# lia_2-0.net
KiCad netlist of a schematic drawn in EAGLE
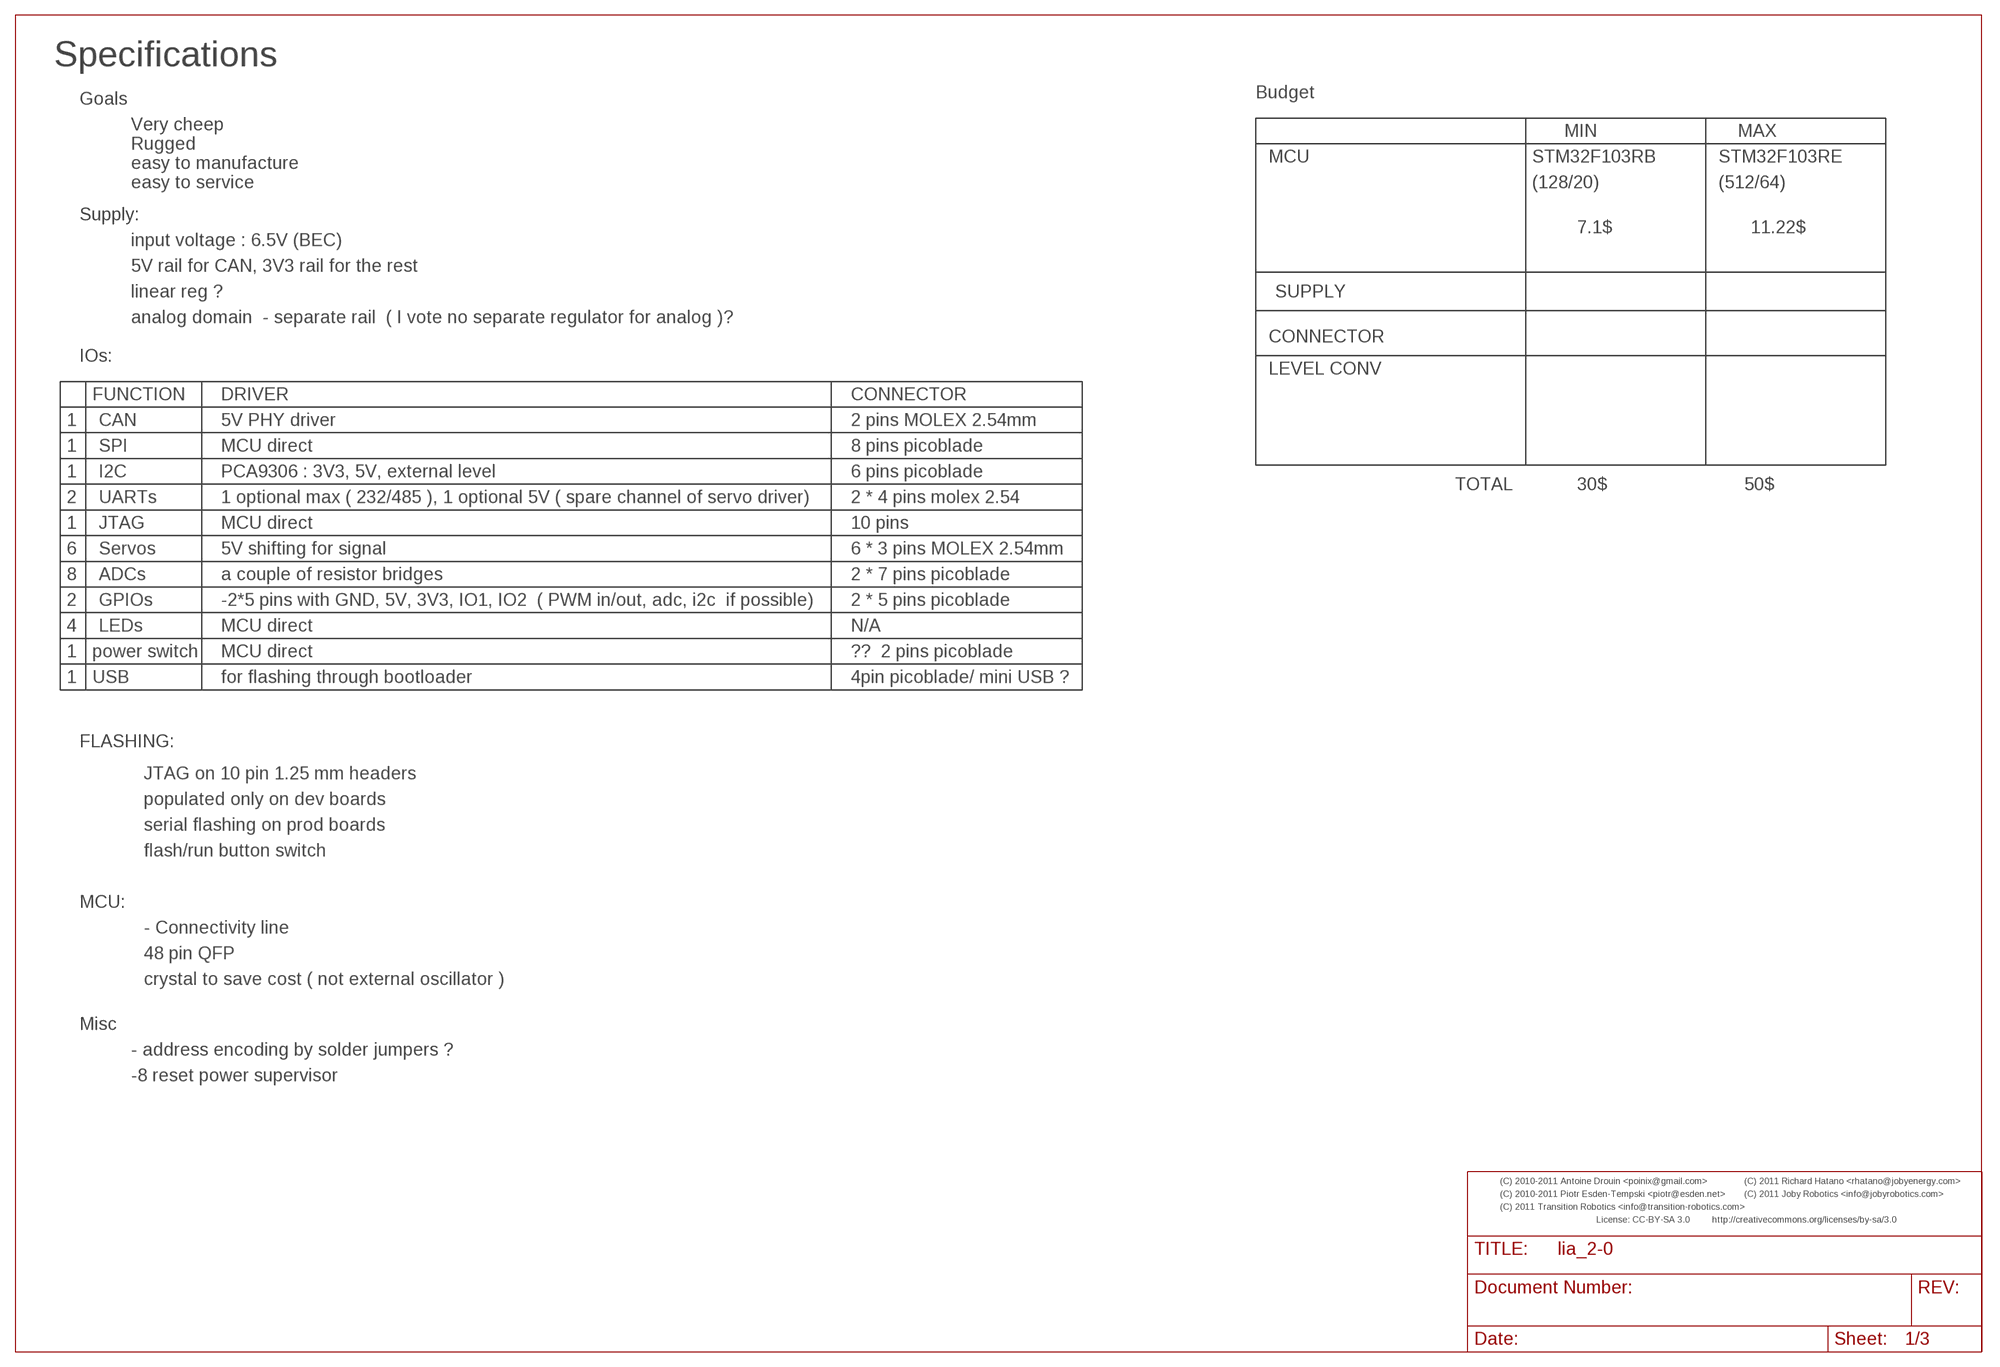
[diagram p0: schematic, sheet 1]
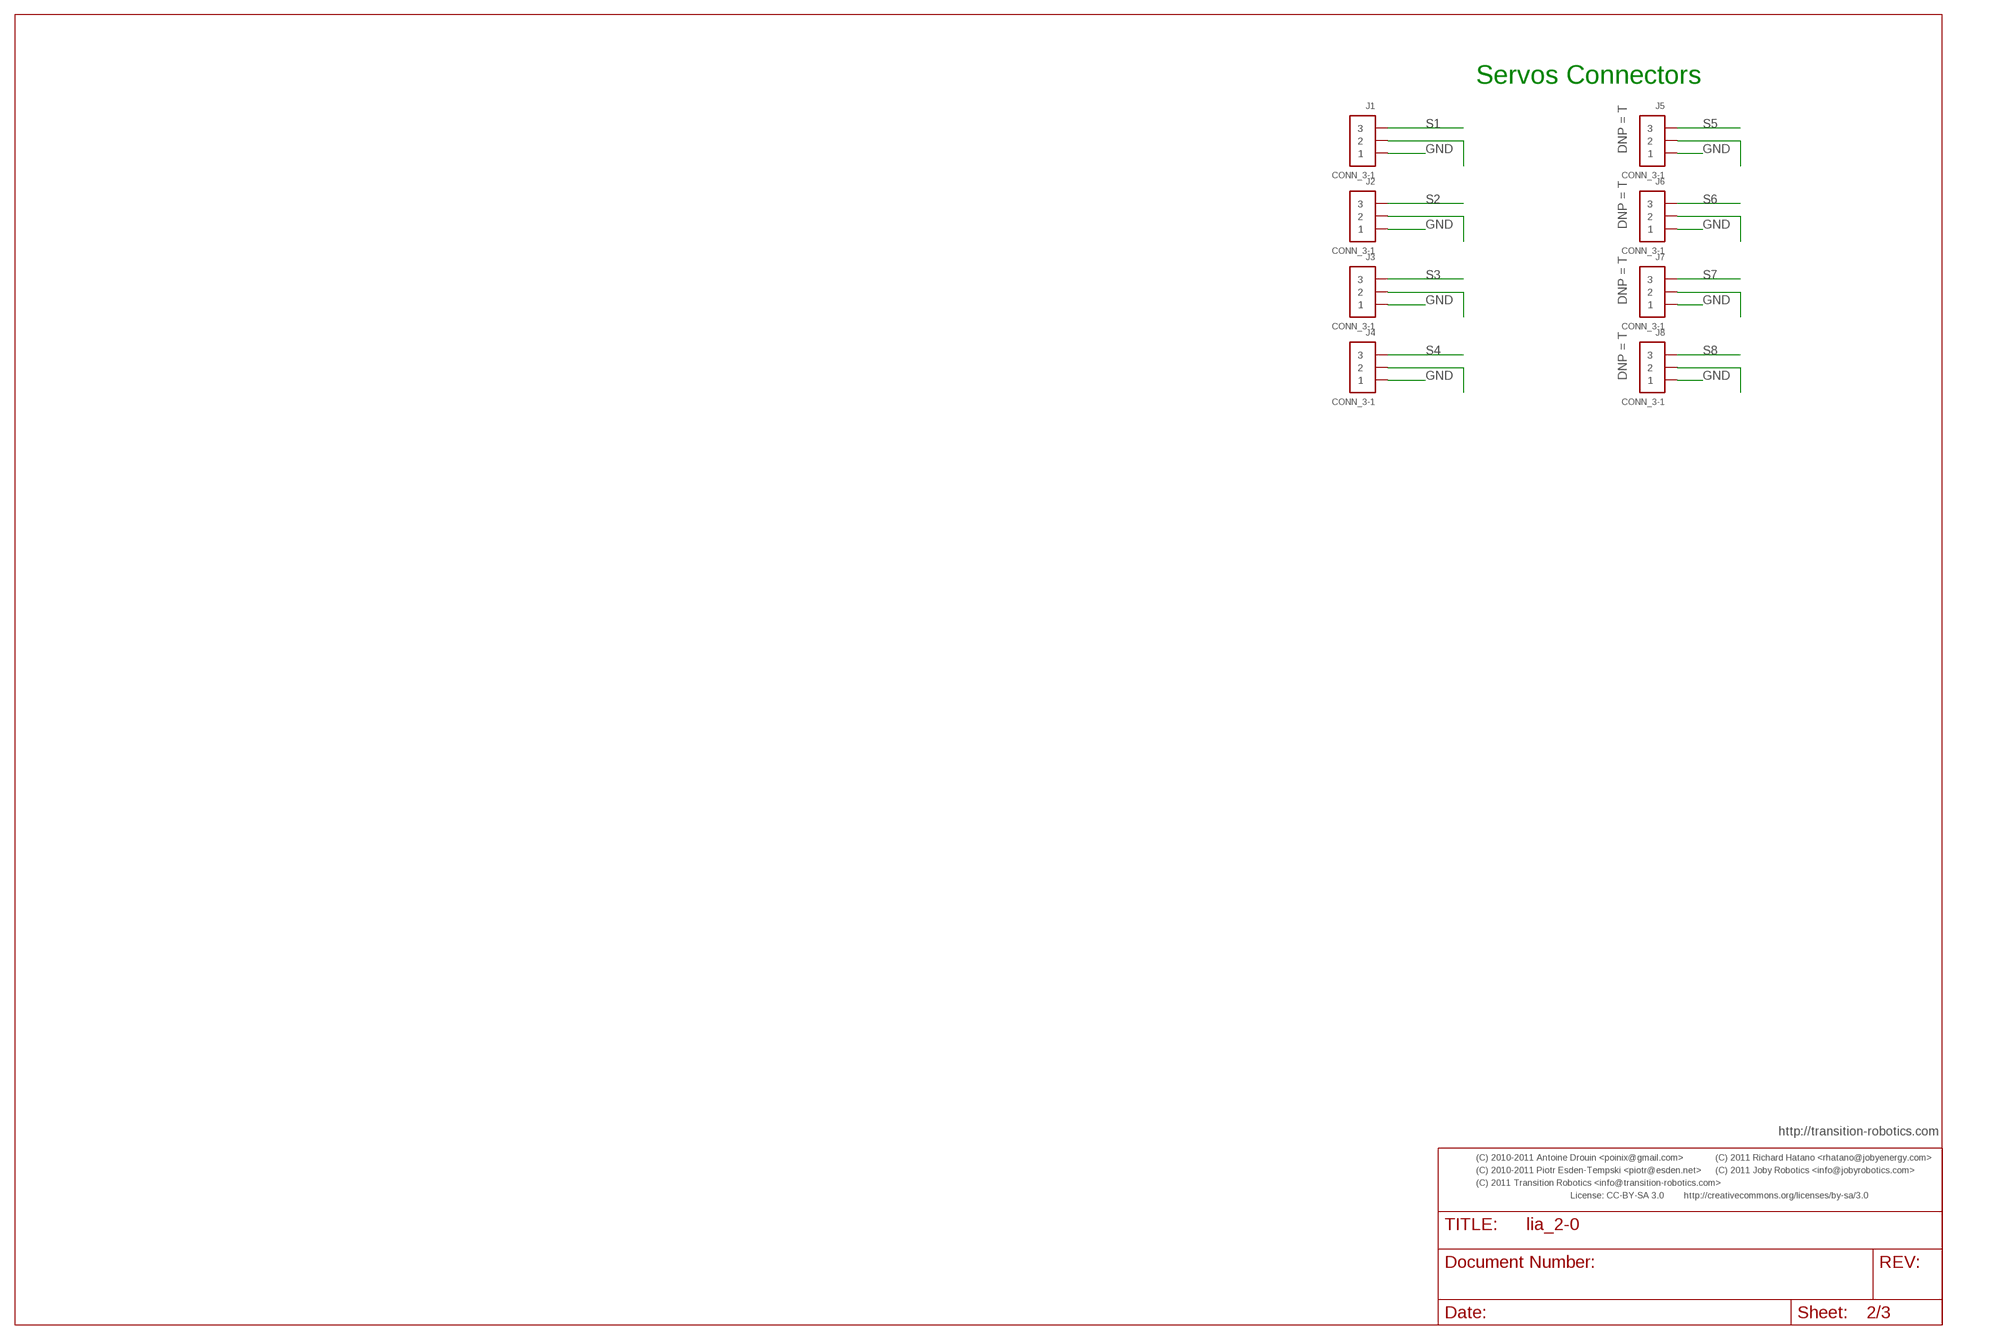
[diagram p1: schematic, sheet 2]
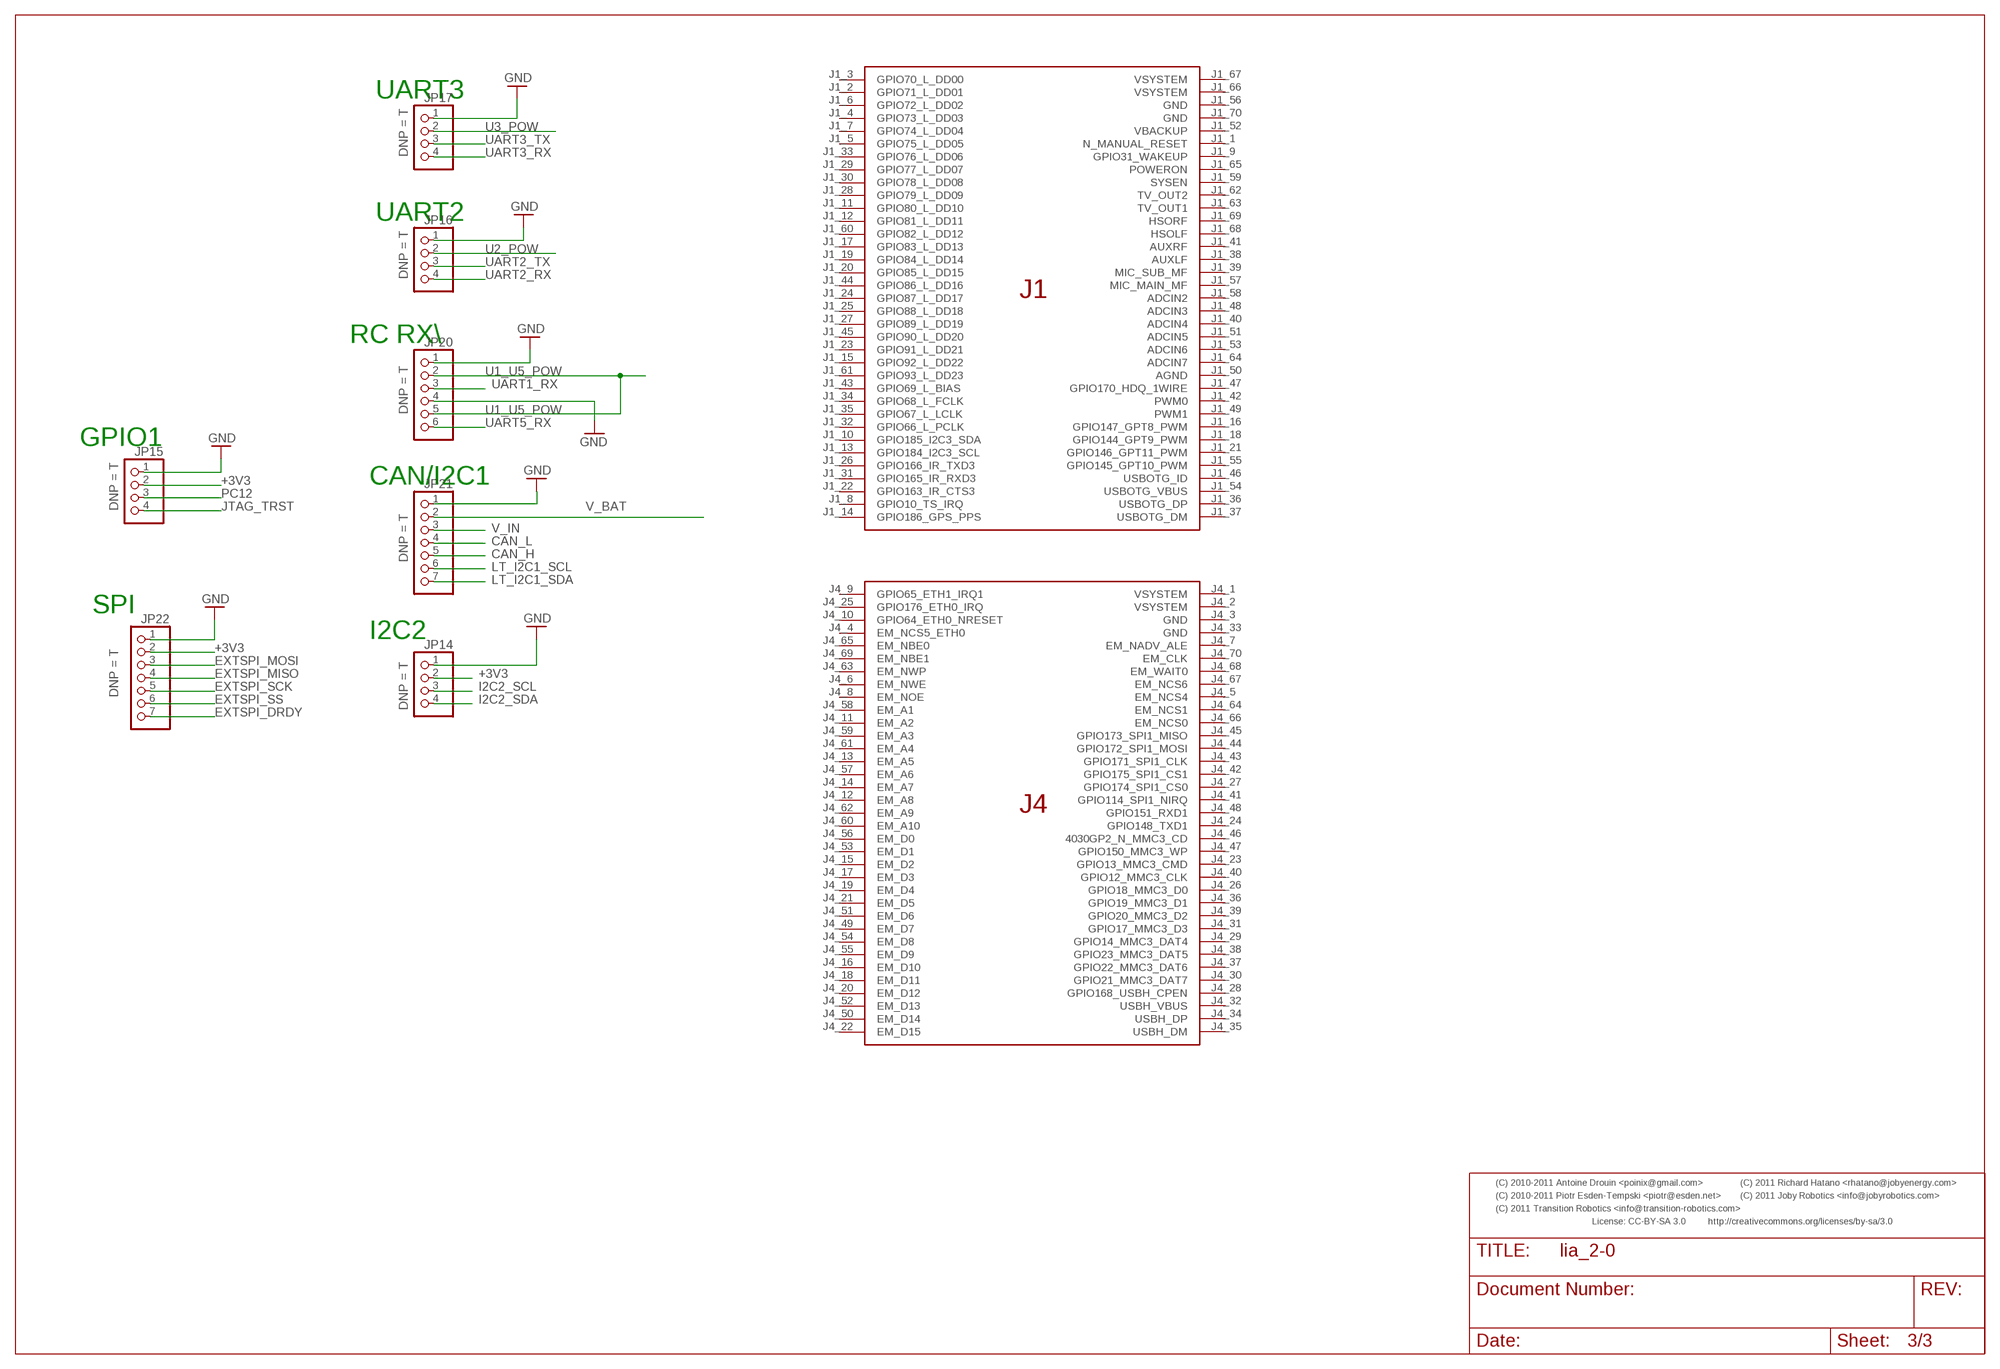
[diagram p2: schematic, sheet 3]

(export (version "E")
  (design (tool "Eeschema 10.0.6"))
  (components
    (comp (ref "JP14")
      (value "PINHD-1X4")
      (footprint "eagle-import:1X04")
      (fields (field (name "DNP") "T") (field (name "PARTNO") "conn-th-0.1in-4-1"))
      (libsource (lib "eagle-import") (part "PINHD-1X4"))
    )
    (comp (ref "JP15")
      (value "PINHD-1X4")
      (footprint "eagle-import:1X04")
      (fields (field (name "DNP") "T") (field (name "PARTNO") "conn-th-0.1in-4-1"))
      (libsource (lib "eagle-import") (part "PINHD-1X4"))
    )
    (comp (ref "JP16")
      (value "PINHD-1X4")
      (footprint "eagle-import:1X04")
      (fields (field (name "DNP") "T") (field (name "PARTNO") "conn-th-0.1in-4-1"))
      (libsource (lib "eagle-import") (part "PINHD-1X4"))
    )
    (comp (ref "JP17")
      (value "PINHD-1X4")
      (footprint "eagle-import:1X04")
      (fields (field (name "DNP") "T") (field (name "PARTNO") "conn-th-0.1in-4-1"))
      (libsource (lib "eagle-import") (part "PINHD-1X4"))
    )
    (comp (ref "JP20")
      (value "PINHD-1X6")
      (footprint "eagle-import:1X06")
      (fields (field (name "DNP") "T") (field (name "PARTNO") "conn-th-0.1in-6-1"))
      (libsource (lib "eagle-import") (part "PINHD-1X6"))
    )
    (comp (ref "JP21")
      (value "PINHD-1X7")
      (footprint "eagle-import:1X07")
      (fields (field (name "DNP") "T") (field (name "PARTNO") "conn-th-0.1in-7-1"))
      (libsource (lib "eagle-import") (part "PINHD-1X7"))
    )
    (comp (ref "JP22")
      (value "PINHD-1X7")
      (footprint "eagle-import:1X07")
      (fields (field (name "DNP") "T") (field (name "PARTNO") "conn-th-0.1in-7-1"))
      (libsource (lib "eagle-import") (part "PINHD-1X7"))
    )
    (comp (ref "U$2")
      (value "OVERO")
      (footprint "eagle-import:OVERO")
      (libsource (lib "eagle-import") (part "OVERO"))
    )
    (comp (ref "J1")
      (value "CONN_3-1")
      (footprint "eagle-import:SIP1X3_100")
      (fields (field (name "PARTNO") "conn-th-0.1in-3-2-ra"))
      (libsource (lib "eagle-import") (part "CONN_3-1"))
    )
    (comp (ref "J2")
      (value "CONN_3-1")
      (footprint "eagle-import:SIP1X3_100")
      (fields (field (name "PARTNO") "conn-th-0.1in-3-2-ra"))
      (libsource (lib "eagle-import") (part "CONN_3-1"))
    )
    (comp (ref "J3")
      (value "CONN_3-1")
      (footprint "eagle-import:SIP1X3_100")
      (fields (field (name "PARTNO") "conn-th-0.1in-3-2-ra"))
      (libsource (lib "eagle-import") (part "CONN_3-1"))
    )
    (comp (ref "J4")
      (value "CONN_3-1")
      (footprint "eagle-import:SIP1X3_100")
      (fields (field (name "PARTNO") "conn-th-0.1in-3-2-ra"))
      (libsource (lib "eagle-import") (part "CONN_3-1"))
    )
    (comp (ref "J5")
      (value "CONN_3-1")
      (footprint "eagle-import:SIP1X3_100")
      (fields (field (name "DNP") "T") (field (name "PARTNO") "conn-th-0.1in-3-2-ra"))
      (libsource (lib "eagle-import") (part "CONN_3-1"))
    )
    (comp (ref "J6")
      (value "CONN_3-1")
      (footprint "eagle-import:SIP1X3_100")
      (fields (field (name "DNP") "T") (field (name "PARTNO") "conn-th-0.1in-3-2-ra"))
      (libsource (lib "eagle-import") (part "CONN_3-1"))
    )
    (comp (ref "J7")
      (value "CONN_3-1")
      (footprint "eagle-import:SIP1X3_100")
      (fields (field (name "DNP") "T") (field (name "PARTNO") "conn-th-0.1in-3-2-ra"))
      (libsource (lib "eagle-import") (part "CONN_3-1"))
    )
    (comp (ref "J8")
      (value "CONN_3-1")
      (footprint "eagle-import:SIP1X3_100")
      (fields (field (name "DNP") "T") (field (name "PARTNO") "conn-th-0.1in-3-2-ra"))
      (libsource (lib "eagle-import") (part "CONN_3-1"))
    )
  )
  (nets
    (net (code "1") (name "+3V3") (class "Default")
      (node (ref "JP14") (pin "2") (pinfunction "2_2") (pintype "passive"))
      (node (ref "JP15") (pin "2") (pinfunction "2_2") (pintype "passive"))
      (node (ref "JP22") (pin "2") (pinfunction "2_2") (pintype "passive"))
    )
    (net (code "2") (name "CAN_H") (class "Default")
      (node (ref "JP21") (pin "5") (pinfunction "5_5") (pintype "passive"))
    )
    (net (code "3") (name "CAN_L") (class "Default")
      (node (ref "JP21") (pin "4") (pinfunction "4_4") (pintype "passive"))
    )
    (net (code "4") (name "EXTSPI_DRDY") (class "Default")
      (node (ref "JP22") (pin "7") (pinfunction "7_7") (pintype "passive"))
    )
    (net (code "5") (name "EXTSPI_MISO") (class "Default")
      (node (ref "JP22") (pin "4") (pinfunction "4_4") (pintype "passive"))
    )
    (net (code "6") (name "EXTSPI_MOSI") (class "Default")
      (node (ref "JP22") (pin "3") (pinfunction "3_3") (pintype "passive"))
    )
    (net (code "7") (name "EXTSPI_SCK") (class "Default")
      (node (ref "JP22") (pin "5") (pinfunction "5_5") (pintype "passive"))
    )
    (net (code "8") (name "EXTSPI_SS") (class "Default")
      (node (ref "JP22") (pin "6") (pinfunction "6_6") (pintype "passive"))
    )
    (net (code "9") (name "GND") (class "Default")
      (node (ref "J1") (pin "1") (pinfunction "1_1") (pintype "bidirectional"))
      (node (ref "J2") (pin "1") (pinfunction "1_1") (pintype "bidirectional"))
      (node (ref "J3") (pin "1") (pinfunction "1_1") (pintype "bidirectional"))
      (node (ref "J4") (pin "1") (pinfunction "1_1") (pintype "bidirectional"))
      (node (ref "J5") (pin "1") (pinfunction "1_1") (pintype "bidirectional"))
      (node (ref "J6") (pin "1") (pinfunction "1_1") (pintype "bidirectional"))
      (node (ref "J7") (pin "1") (pinfunction "1_1") (pintype "bidirectional"))
      (node (ref "J8") (pin "1") (pinfunction "1_1") (pintype "bidirectional"))
      (node (ref "JP14") (pin "1") (pinfunction "1_1") (pintype "passive"))
      (node (ref "JP15") (pin "1") (pinfunction "1_1") (pintype "passive"))
      (node (ref "JP16") (pin "1") (pinfunction "1_1") (pintype "passive"))
      (node (ref "JP17") (pin "1") (pinfunction "1_1") (pintype "passive"))
      (node (ref "JP20") (pin "1") (pinfunction "1_1") (pintype "passive"))
      (node (ref "JP20") (pin "4") (pinfunction "4_4") (pintype "passive"))
      (node (ref "JP21") (pin "1") (pinfunction "1_1") (pintype "passive"))
      (node (ref "JP22") (pin "1") (pinfunction "1_1") (pintype "passive"))
    )
    (net (code "10") (name "I2C2_SCL") (class "Default")
      (node (ref "JP14") (pin "3") (pinfunction "3_3") (pintype "passive"))
    )
    (net (code "11") (name "I2C2_SDA") (class "Default")
      (node (ref "JP14") (pin "4") (pinfunction "4_4") (pintype "passive"))
    )
    (net (code "12") (name "JTAG_TRST") (class "Default")
      (node (ref "JP15") (pin "4") (pinfunction "4_4") (pintype "passive"))
    )
    (net (code "13") (name "LT_I2C1_SCL") (class "Default")
      (node (ref "JP21") (pin "6") (pinfunction "6_6") (pintype "passive"))
    )
    (net (code "14") (name "LT_I2C1_SDA") (class "Default")
      (node (ref "JP21") (pin "7") (pinfunction "7_7") (pintype "passive"))
    )
    (net (code "15") (name "PC12") (class "Default")
      (node (ref "JP15") (pin "3") (pinfunction "3_3") (pintype "passive"))
    )
    (net (code "16") (name "S1") (class "Default")
      (node (ref "J1") (pin "3") (pinfunction "3_3") (pintype "bidirectional"))
    )
    (net (code "17") (name "S2") (class "Default")
      (node (ref "J2") (pin "3") (pinfunction "3_3") (pintype "bidirectional"))
    )
    (net (code "18") (name "S3") (class "Default")
      (node (ref "J3") (pin "3") (pinfunction "3_3") (pintype "bidirectional"))
    )
    (net (code "19") (name "S4") (class "Default")
      (node (ref "J4") (pin "3") (pinfunction "3_3") (pintype "bidirectional"))
    )
    (net (code "20") (name "S5") (class "Default")
      (node (ref "J5") (pin "3") (pinfunction "3_3") (pintype "bidirectional"))
    )
    (net (code "21") (name "S6") (class "Default")
      (node (ref "J6") (pin "3") (pinfunction "3_3") (pintype "bidirectional"))
    )
    (net (code "22") (name "S7") (class "Default")
      (node (ref "J7") (pin "3") (pinfunction "3_3") (pintype "bidirectional"))
    )
    (net (code "23") (name "S8") (class "Default")
      (node (ref "J8") (pin "3") (pinfunction "3_3") (pintype "bidirectional"))
    )
    (net (code "24") (name "U1_U5_POW") (class "Default")
      (node (ref "JP20") (pin "2") (pinfunction "2_2") (pintype "passive"))
      (node (ref "JP20") (pin "5") (pinfunction "5_5") (pintype "passive"))
    )
    (net (code "25") (name "U2_POW") (class "Default")
      (node (ref "JP16") (pin "2") (pinfunction "2_2") (pintype "passive"))
    )
    (net (code "26") (name "U3_POW") (class "Default")
      (node (ref "JP17") (pin "2") (pinfunction "2_2") (pintype "passive"))
    )
    (net (code "27") (name "UART1_RX") (class "Default")
      (node (ref "JP20") (pin "3") (pinfunction "3_3") (pintype "passive"))
    )
    (net (code "28") (name "UART2_RX") (class "Default")
      (node (ref "JP16") (pin "4") (pinfunction "4_4") (pintype "passive"))
    )
    (net (code "29") (name "UART2_TX") (class "Default")
      (node (ref "JP16") (pin "3") (pinfunction "3_3") (pintype "passive"))
    )
    (net (code "30") (name "UART3_RX") (class "Default")
      (node (ref "JP17") (pin "4") (pinfunction "4_4") (pintype "passive"))
    )
    (net (code "31") (name "UART3_TX") (class "Default")
      (node (ref "JP17") (pin "3") (pinfunction "3_3") (pintype "passive"))
    )
    (net (code "32") (name "UART5_RX") (class "Default")
      (node (ref "JP20") (pin "6") (pinfunction "6_6") (pintype "passive"))
    )
    (net (code "33") (name "V_BAT") (class "Default")
      (node (ref "JP21") (pin "2") (pinfunction "2_2") (pintype "passive"))
    )
    (net (code "34") (name "V_IN") (class "Default")
      (node (ref "JP21") (pin "3") (pinfunction "3_3") (pintype "passive"))
    )
    (net (code "35") (name "unconnected-(J1-Pad2)") (class "Default")
      (node (ref "J1") (pin "2") (pinfunction "2_2") (pintype "bidirectional"))
    )
    (net (code "36") (name "unconnected-(J2-Pad2)") (class "Default")
      (node (ref "J2") (pin "2") (pinfunction "2_2") (pintype "bidirectional"))
    )
    (net (code "37") (name "unconnected-(J3-Pad2)") (class "Default")
      (node (ref "J3") (pin "2") (pinfunction "2_2") (pintype "bidirectional"))
    )
    (net (code "38") (name "unconnected-(J4-Pad2)") (class "Default")
      (node (ref "J4") (pin "2") (pinfunction "2_2") (pintype "bidirectional"))
    )
    (net (code "39") (name "unconnected-(J5-Pad2)") (class "Default")
      (node (ref "J5") (pin "2") (pinfunction "2_2") (pintype "bidirectional"))
    )
    (net (code "40") (name "unconnected-(J6-Pad2)") (class "Default")
      (node (ref "J6") (pin "2") (pinfunction "2_2") (pintype "bidirectional"))
    )
    (net (code "41") (name "unconnected-(J7-Pad2)") (class "Default")
      (node (ref "J7") (pin "2") (pinfunction "2_2") (pintype "bidirectional"))
    )
    (net (code "42") (name "unconnected-(J8-Pad2)") (class "Default")
      (node (ref "J8") (pin "2") (pinfunction "2_2") (pintype "bidirectional"))
    )
    (net (code "43") (name "unconnected-(U$2-4030GP2_N_MMC3_CD-PadJ4_46)") (class "Default")
      (node (ref "U$2") (pin "J4_46") (pinfunction "4030GP2_N_MMC3_CD_J4_46") (pintype "bidirectional"))
    )
    (net (code "44") (name "unconnected-(U$2-ADCIN2-PadJ1_58)") (class "Default")
      (node (ref "U$2") (pin "J1_58") (pinfunction "ADCIN2_J1_58") (pintype "bidirectional"))
    )
    (net (code "45") (name "unconnected-(U$2-ADCIN3-PadJ1_48)") (class "Default")
      (node (ref "U$2") (pin "J1_48") (pinfunction "ADCIN3_J1_48") (pintype "bidirectional"))
    )
    (net (code "46") (name "unconnected-(U$2-ADCIN4-PadJ1_40)") (class "Default")
      (node (ref "U$2") (pin "J1_40") (pinfunction "ADCIN4_J1_40") (pintype "bidirectional"))
    )
    (net (code "47") (name "unconnected-(U$2-ADCIN5-PadJ1_51)") (class "Default")
      (node (ref "U$2") (pin "J1_51") (pinfunction "ADCIN5_J1_51") (pintype "bidirectional"))
    )
    (net (code "48") (name "unconnected-(U$2-ADCIN6-PadJ1_53)") (class "Default")
      (node (ref "U$2") (pin "J1_53") (pinfunction "ADCIN6_J1_53") (pintype "bidirectional"))
    )
    (net (code "49") (name "unconnected-(U$2-ADCIN7-PadJ1_64)") (class "Default")
      (node (ref "U$2") (pin "J1_64") (pinfunction "ADCIN7_J1_64") (pintype "bidirectional"))
    )
    (net (code "50") (name "unconnected-(U$2-AGND-PadJ1_50)") (class "Default")
      (node (ref "U$2") (pin "J1_50") (pinfunction "AGND_J1_50") (pintype "bidirectional"))
    )
    (net (code "51") (name "unconnected-(U$2-AUXLF-PadJ1_38)") (class "Default")
      (node (ref "U$2") (pin "J1_38") (pinfunction "AUXLF_J1_38") (pintype "bidirectional"))
    )
    (net (code "52") (name "unconnected-(U$2-AUXRF-PadJ1_41)") (class "Default")
      (node (ref "U$2") (pin "J1_41") (pinfunction "AUXRF_J1_41") (pintype "bidirectional"))
    )
    (net (code "53") (name "unconnected-(U$2-EM_A1-PadJ4_58)") (class "Default")
      (node (ref "U$2") (pin "J4_58") (pinfunction "EM_A1_J4_58") (pintype "bidirectional"))
    )
    (net (code "54") (name "unconnected-(U$2-EM_A2-PadJ4_11)") (class "Default")
      (node (ref "U$2") (pin "J4_11") (pinfunction "EM_A2_J4_11") (pintype "bidirectional"))
    )
    (net (code "55") (name "unconnected-(U$2-EM_A3-PadJ4_59)") (class "Default")
      (node (ref "U$2") (pin "J4_59") (pinfunction "EM_A3_J4_59") (pintype "bidirectional"))
    )
    (net (code "56") (name "unconnected-(U$2-EM_A4-PadJ4_61)") (class "Default")
      (node (ref "U$2") (pin "J4_61") (pinfunction "EM_A4_J4_61") (pintype "bidirectional"))
    )
    (net (code "57") (name "unconnected-(U$2-EM_A5-PadJ4_13)") (class "Default")
      (node (ref "U$2") (pin "J4_13") (pinfunction "EM_A5_J4_13") (pintype "bidirectional"))
    )
    (net (code "58") (name "unconnected-(U$2-EM_A6-PadJ4_57)") (class "Default")
      (node (ref "U$2") (pin "J4_57") (pinfunction "EM_A6_J4_57") (pintype "bidirectional"))
    )
    (net (code "59") (name "unconnected-(U$2-EM_A7-PadJ4_14)") (class "Default")
      (node (ref "U$2") (pin "J4_14") (pinfunction "EM_A7_J4_14") (pintype "bidirectional"))
    )
    (net (code "60") (name "unconnected-(U$2-EM_A8-PadJ4_12)") (class "Default")
      (node (ref "U$2") (pin "J4_12") (pinfunction "EM_A8_J4_12") (pintype "bidirectional"))
    )
    (net (code "61") (name "unconnected-(U$2-EM_A9-PadJ4_62)") (class "Default")
      (node (ref "U$2") (pin "J4_62") (pinfunction "EM_A9_J4_62") (pintype "bidirectional"))
    )
    (net (code "62") (name "unconnected-(U$2-EM_A10-PadJ4_60)") (class "Default")
      (node (ref "U$2") (pin "J4_60") (pinfunction "EM_A10_J4_60") (pintype "bidirectional"))
    )
    (net (code "63") (name "unconnected-(U$2-EM_CLK-PadJ4_70)") (class "Default")
      (node (ref "U$2") (pin "J4_70") (pinfunction "EM_CLK_J4_70") (pintype "bidirectional"))
    )
    (net (code "64") (name "unconnected-(U$2-EM_D0-PadJ4_56)") (class "Default")
      (node (ref "U$2") (pin "J4_56") (pinfunction "EM_D0_J4_56") (pintype "bidirectional"))
    )
    (net (code "65") (name "unconnected-(U$2-EM_D1-PadJ4_53)") (class "Default")
      (node (ref "U$2") (pin "J4_53") (pinfunction "EM_D1_J4_53") (pintype "bidirectional"))
    )
    (net (code "66") (name "unconnected-(U$2-EM_D2-PadJ4_15)") (class "Default")
      (node (ref "U$2") (pin "J4_15") (pinfunction "EM_D2_J4_15") (pintype "bidirectional"))
    )
    (net (code "67") (name "unconnected-(U$2-EM_D3-PadJ4_17)") (class "Default")
      (node (ref "U$2") (pin "J4_17") (pinfunction "EM_D3_J4_17") (pintype "bidirectional"))
    )
    (net (code "68") (name "unconnected-(U$2-EM_D4-PadJ4_19)") (class "Default")
      (node (ref "U$2") (pin "J4_19") (pinfunction "EM_D4_J4_19") (pintype "bidirectional"))
    )
    (net (code "69") (name "unconnected-(U$2-EM_D5-PadJ4_21)") (class "Default")
      (node (ref "U$2") (pin "J4_21") (pinfunction "EM_D5_J4_21") (pintype "bidirectional"))
    )
    (net (code "70") (name "unconnected-(U$2-EM_D6-PadJ4_51)") (class "Default")
      (node (ref "U$2") (pin "J4_51") (pinfunction "EM_D6_J4_51") (pintype "bidirectional"))
    )
    (net (code "71") (name "unconnected-(U$2-EM_D7-PadJ4_49)") (class "Default")
      (node (ref "U$2") (pin "J4_49") (pinfunction "EM_D7_J4_49") (pintype "bidirectional"))
    )
    (net (code "72") (name "unconnected-(U$2-EM_D8-PadJ4_54)") (class "Default")
      (node (ref "U$2") (pin "J4_54") (pinfunction "EM_D8_J4_54") (pintype "bidirectional"))
    )
    (net (code "73") (name "unconnected-(U$2-EM_D9-PadJ4_55)") (class "Default")
      (node (ref "U$2") (pin "J4_55") (pinfunction "EM_D9_J4_55") (pintype "bidirectional"))
    )
    (net (code "74") (name "unconnected-(U$2-EM_D10-PadJ4_16)") (class "Default")
      (node (ref "U$2") (pin "J4_16") (pinfunction "EM_D10_J4_16") (pintype "bidirectional"))
    )
    (net (code "75") (name "unconnected-(U$2-EM_D11-PadJ4_18)") (class "Default")
      (node (ref "U$2") (pin "J4_18") (pinfunction "EM_D11_J4_18") (pintype "bidirectional"))
    )
    (net (code "76") (name "unconnected-(U$2-EM_D12-PadJ4_20)") (class "Default")
      (node (ref "U$2") (pin "J4_20") (pinfunction "EM_D12_J4_20") (pintype "bidirectional"))
    )
    (net (code "77") (name "unconnected-(U$2-EM_D13-PadJ4_52)") (class "Default")
      (node (ref "U$2") (pin "J4_52") (pinfunction "EM_D13_J4_52") (pintype "bidirectional"))
    )
    (net (code "78") (name "unconnected-(U$2-EM_D14-PadJ4_50)") (class "Default")
      (node (ref "U$2") (pin "J4_50") (pinfunction "EM_D14_J4_50") (pintype "bidirectional"))
    )
    (net (code "79") (name "unconnected-(U$2-EM_D15-PadJ4_22)") (class "Default")
      (node (ref "U$2") (pin "J4_22") (pinfunction "EM_D15_J4_22") (pintype "bidirectional"))
    )
    (net (code "80") (name "unconnected-(U$2-EM_NADV_ALE-PadJ4_7)") (class "Default")
      (node (ref "U$2") (pin "J4_7") (pinfunction "EM_NADV_ALE_J4_7") (pintype "bidirectional"))
    )
    (net (code "81") (name "unconnected-(U$2-EM_NBE0-PadJ4_65)") (class "Default")
      (node (ref "U$2") (pin "J4_65") (pinfunction "EM_NBE0_J4_65") (pintype "bidirectional"))
    )
    (net (code "82") (name "unconnected-(U$2-EM_NBE1-PadJ4_69)") (class "Default")
      (node (ref "U$2") (pin "J4_69") (pinfunction "EM_NBE1_J4_69") (pintype "bidirectional"))
    )
    (net (code "83") (name "unconnected-(U$2-EM_NCS0-PadJ4_66)") (class "Default")
      (node (ref "U$2") (pin "J4_66") (pinfunction "EM_NCS0_J4_66") (pintype "bidirectional"))
    )
    (net (code "84") (name "unconnected-(U$2-EM_NCS1-PadJ4_64)") (class "Default")
      (node (ref "U$2") (pin "J4_64") (pinfunction "EM_NCS1_J4_64") (pintype "bidirectional"))
    )
    (net (code "85") (name "unconnected-(U$2-EM_NCS4-PadJ4_5)") (class "Default")
      (node (ref "U$2") (pin "J4_5") (pinfunction "EM_NCS4_J4_5") (pintype "bidirectional"))
    )
    (net (code "86") (name "unconnected-(U$2-EM_NCS5_ETH0-PadJ4_4)") (class "Default")
      (node (ref "U$2") (pin "J4_4") (pinfunction "EM_NCS5_ETH0_J4_4") (pintype "bidirectional"))
    )
    (net (code "87") (name "unconnected-(U$2-EM_NCS6-PadJ4_67)") (class "Default")
      (node (ref "U$2") (pin "J4_67") (pinfunction "EM_NCS6_J4_67") (pintype "bidirectional"))
    )
    (net (code "88") (name "unconnected-(U$2-EM_NOE-PadJ4_8)") (class "Default")
      (node (ref "U$2") (pin "J4_8") (pinfunction "EM_NOE_J4_8") (pintype "bidirectional"))
    )
    (net (code "89") (name "unconnected-(U$2-EM_NWE-PadJ4_6)") (class "Default")
      (node (ref "U$2") (pin "J4_6") (pinfunction "EM_NWE_J4_6") (pintype "bidirectional"))
    )
    (net (code "90") (name "unconnected-(U$2-EM_NWP-PadJ4_63)") (class "Default")
      (node (ref "U$2") (pin "J4_63") (pinfunction "EM_NWP_J4_63") (pintype "bidirectional"))
    )
    (net (code "91") (name "unconnected-(U$2-EM_WAIT0-PadJ4_68)") (class "Default")
      (node (ref "U$2") (pin "J4_68") (pinfunction "EM_WAIT0_J4_68") (pintype "bidirectional"))
    )
    (net (code "92") (name "unconnected-(U$2-GND-PadJ1_56)") (class "Default")
      (node (ref "U$2") (pin "J1_56") (pinfunction "GND_J1_56") (pintype "bidirectional"))
    )
    (net (code "93") (name "unconnected-(U$2-GND-PadJ1_70)") (class "Default")
      (node (ref "U$2") (pin "J1_70") (pinfunction "GND_J1_70") (pintype "bidirectional"))
    )
    (net (code "94") (name "unconnected-(U$2-GND-PadJ4_3)") (class "Default")
      (node (ref "U$2") (pin "J4_3") (pinfunction "GND_J4_3") (pintype "bidirectional"))
    )
    (net (code "95") (name "unconnected-(U$2-GND-PadJ4_33)") (class "Default")
      (node (ref "U$2") (pin "J4_33") (pinfunction "GND_J4_33") (pintype "bidirectional"))
    )
    (net (code "96") (name "unconnected-(U$2-GPIO10_TS_IRQ-PadJ1_8)") (class "Default")
      (node (ref "U$2") (pin "J1_8") (pinfunction "GPIO10_TS_IRQ_J1_8") (pintype "bidirectional"))
    )
    (net (code "97") (name "unconnected-(U$2-GPIO12_MMC3_CLK-PadJ4_40)") (class "Default")
      (node (ref "U$2") (pin "J4_40") (pinfunction "GPIO12_MMC3_CLK_J4_40") (pintype "bidirectional"))
    )
    (net (code "98") (name "unconnected-(U$2-GPIO13_MMC3_CMD-PadJ4_23)") (class "Default")
      (node (ref "U$2") (pin "J4_23") (pinfunction "GPIO13_MMC3_CMD_J4_23") (pintype "bidirectional"))
    )
    (net (code "99") (name "unconnected-(U$2-GPIO14_MMC3_DAT4-PadJ4_29)") (class "Default")
      (node (ref "U$2") (pin "J4_29") (pinfunction "GPIO14_MMC3_DAT4_J4_29") (pintype "bidirectional"))
    )
    (net (code "100") (name "unconnected-(U$2-GPIO17_MMC3_D3-PadJ4_31)") (class "Default")
      (node (ref "U$2") (pin "J4_31") (pinfunction "GPIO17_MMC3_D3_J4_31") (pintype "bidirectional"))
    )
    (net (code "101") (name "unconnected-(U$2-GPIO18_MMC3_D0-PadJ4_26)") (class "Default")
      (node (ref "U$2") (pin "J4_26") (pinfunction "GPIO18_MMC3_D0_J4_26") (pintype "bidirectional"))
    )
    (net (code "102") (name "unconnected-(U$2-GPIO19_MMC3_D1-PadJ4_36)") (class "Default")
      (node (ref "U$2") (pin "J4_36") (pinfunction "GPIO19_MMC3_D1_J4_36") (pintype "bidirectional"))
    )
    (net (code "103") (name "unconnected-(U$2-GPIO20_MMC3_D2-PadJ4_39)") (class "Default")
      (node (ref "U$2") (pin "J4_39") (pinfunction "GPIO20_MMC3_D2_J4_39") (pintype "bidirectional"))
    )
    (net (code "104") (name "unconnected-(U$2-GPIO21_MMC3_DAT7-PadJ4_30)") (class "Default")
      (node (ref "U$2") (pin "J4_30") (pinfunction "GPIO21_MMC3_DAT7_J4_30") (pintype "bidirectional"))
    )
    (net (code "105") (name "unconnected-(U$2-GPIO22_MMC3_DAT6-PadJ4_37)") (class "Default")
      (node (ref "U$2") (pin "J4_37") (pinfunction "GPIO22_MMC3_DAT6_J4_37") (pintype "bidirectional"))
    )
    (net (code "106") (name "unconnected-(U$2-GPIO23_MMC3_DAT5-PadJ4_38)") (class "Default")
      (node (ref "U$2") (pin "J4_38") (pinfunction "GPIO23_MMC3_DAT5_J4_38") (pintype "bidirectional"))
    )
    (net (code "107") (name "unconnected-(U$2-GPIO31_WAKEUP-PadJ1_9)") (class "Default")
      (node (ref "U$2") (pin "J1_9") (pinfunction "GPIO31_WAKEUP_J1_9") (pintype "bidirectional"))
    )
    (net (code "108") (name "unconnected-(U$2-GPIO64_ETH0_NRESET-PadJ4_10)") (class "Default")
      (node (ref "U$2") (pin "J4_10") (pinfunction "GPIO64_ETH0_NRESET_J4_10") (pintype "bidirectional"))
    )
    (net (code "109") (name "unconnected-(U$2-GPIO65_ETH1_IRQ1-PadJ4_9)") (class "Default")
      (node (ref "U$2") (pin "J4_9") (pinfunction "GPIO65_ETH1_IRQ1_J4_9") (pintype "bidirectional"))
    )
    (net (code "110") (name "unconnected-(U$2-GPIO66_L_PCLK-PadJ1_32)") (class "Default")
      (node (ref "U$2") (pin "J1_32") (pinfunction "GPIO66_L_PCLK_J1_32") (pintype "bidirectional"))
    )
    (net (code "111") (name "unconnected-(U$2-GPIO67_L_LCLK-PadJ1_35)") (class "Default")
      (node (ref "U$2") (pin "J1_35") (pinfunction "GPIO67_L_LCLK_J1_35") (pintype "bidirectional"))
    )
    (net (code "112") (name "unconnected-(U$2-GPIO68_L_FCLK-PadJ1_34)") (class "Default")
      (node (ref "U$2") (pin "J1_34") (pinfunction "GPIO68_L_FCLK_J1_34") (pintype "bidirectional"))
    )
    (net (code "113") (name "unconnected-(U$2-GPIO69_L_BIAS-PadJ1_43)") (class "Default")
      (node (ref "U$2") (pin "J1_43") (pinfunction "GPIO69_L_BIAS_J1_43") (pintype "bidirectional"))
    )
    (net (code "114") (name "unconnected-(U$2-GPIO70_L_DD00-PadJ1_3)") (class "Default")
      (node (ref "U$2") (pin "J1_3") (pinfunction "GPIO70_L_DD00_J1_3") (pintype "bidirectional"))
    )
    (net (code "115") (name "unconnected-(U$2-GPIO71_L_DD01-PadJ1_2)") (class "Default")
      (node (ref "U$2") (pin "J1_2") (pinfunction "GPIO71_L_DD01_J1_2") (pintype "bidirectional"))
    )
    (net (code "116") (name "unconnected-(U$2-GPIO72_L_DD02-PadJ1_6)") (class "Default")
      (node (ref "U$2") (pin "J1_6") (pinfunction "GPIO72_L_DD02_J1_6") (pintype "bidirectional"))
    )
    (net (code "117") (name "unconnected-(U$2-GPIO73_L_DD03-PadJ1_4)") (class "Default")
      (node (ref "U$2") (pin "J1_4") (pinfunction "GPIO73_L_DD03_J1_4") (pintype "bidirectional"))
    )
    (net (code "118") (name "unconnected-(U$2-GPIO74_L_DD04-PadJ1_7)") (class "Default")
      (node (ref "U$2") (pin "J1_7") (pinfunction "GPIO74_L_DD04_J1_7") (pintype "bidirectional"))
    )
    (net (code "119") (name "unconnected-(U$2-GPIO75_L_DD05-PadJ1_5)") (class "Default")
      (node (ref "U$2") (pin "J1_5") (pinfunction "GPIO75_L_DD05_J1_5") (pintype "bidirectional"))
    )
    (net (code "120") (name "unconnected-(U$2-GPIO76_L_DD06-PadJ1_33)") (class "Default")
      (node (ref "U$2") (pin "J1_33") (pinfunction "GPIO76_L_DD06_J1_33") (pintype "bidirectional"))
    )
    (net (code "121") (name "unconnected-(U$2-GPIO77_L_DD07-PadJ1_29)") (class "Default")
      (node (ref "U$2") (pin "J1_29") (pinfunction "GPIO77_L_DD07_J1_29") (pintype "bidirectional"))
    )
    (net (code "122") (name "unconnected-(U$2-GPIO78_L_DD08-PadJ1_30)") (class "Default")
      (node (ref "U$2") (pin "J1_30") (pinfunction "GPIO78_L_DD08_J1_30") (pintype "bidirectional"))
    )
    (net (code "123") (name "unconnected-(U$2-GPIO79_L_DD09-PadJ1_28)") (class "Default")
      (node (ref "U$2") (pin "J1_28") (pinfunction "GPIO79_L_DD09_J1_28") (pintype "bidirectional"))
    )
    (net (code "124") (name "unconnected-(U$2-GPIO80_L_DD10-PadJ1_11)") (class "Default")
      (node (ref "U$2") (pin "J1_11") (pinfunction "GPIO80_L_DD10_J1_11") (pintype "bidirectional"))
    )
    (net (code "125") (name "unconnected-(U$2-GPIO81_L_DD11-PadJ1_12)") (class "Default")
      (node (ref "U$2") (pin "J1_12") (pinfunction "GPIO81_L_DD11_J1_12") (pintype "bidirectional"))
    )
    (net (code "126") (name "unconnected-(U$2-GPIO82_L_DD12-PadJ1_60)") (class "Default")
      (node (ref "U$2") (pin "J1_60") (pinfunction "GPIO82_L_DD12_J1_60") (pintype "bidirectional"))
    )
    (net (code "127") (name "unconnected-(U$2-GPIO83_L_DD13-PadJ1_17)") (class "Default")
      (node (ref "U$2") (pin "J1_17") (pinfunction "GPIO83_L_DD13_J1_17") (pintype "bidirectional"))
    )
    (net (code "128") (name "unconnected-(U$2-GPIO84_L_DD14-PadJ1_19)") (class "Default")
      (node (ref "U$2") (pin "J1_19") (pinfunction "GPIO84_L_DD14_J1_19") (pintype "bidirectional"))
    )
    (net (code "129") (name "unconnected-(U$2-GPIO85_L_DD15-PadJ1_20)") (class "Default")
      (node (ref "U$2") (pin "J1_20") (pinfunction "GPIO85_L_DD15_J1_20") (pintype "bidirectional"))
    )
    (net (code "130") (name "unconnected-(U$2-GPIO86_L_DD16-PadJ1_44)") (class "Default")
      (node (ref "U$2") (pin "J1_44") (pinfunction "GPIO86_L_DD16_J1_44") (pintype "bidirectional"))
    )
    (net (code "131") (name "unconnected-(U$2-GPIO87_L_DD17-PadJ1_24)") (class "Default")
      (node (ref "U$2") (pin "J1_24") (pinfunction "GPIO87_L_DD17_J1_24") (pintype "bidirectional"))
    )
    (net (code "132") (name "unconnected-(U$2-GPIO88_L_DD18-PadJ1_25)") (class "Default")
      (node (ref "U$2") (pin "J1_25") (pinfunction "GPIO88_L_DD18_J1_25") (pintype "bidirectional"))
    )
    (net (code "133") (name "unconnected-(U$2-GPIO89_L_DD19-PadJ1_27)") (class "Default")
      (node (ref "U$2") (pin "J1_27") (pinfunction "GPIO89_L_DD19_J1_27") (pintype "bidirectional"))
    )
    (net (code "134") (name "unconnected-(U$2-GPIO90_L_DD20-PadJ1_45)") (class "Default")
      (node (ref "U$2") (pin "J1_45") (pinfunction "GPIO90_L_DD20_J1_45") (pintype "bidirectional"))
    )
    (net (code "135") (name "unconnected-(U$2-GPIO91_L_DD21-PadJ1_23)") (class "Default")
      (node (ref "U$2") (pin "J1_23") (pinfunction "GPIO91_L_DD21_J1_23") (pintype "bidirectional"))
    )
    (net (code "136") (name "unconnected-(U$2-GPIO92_L_DD22-PadJ1_15)") (class "Default")
      (node (ref "U$2") (pin "J1_15") (pinfunction "GPIO92_L_DD22_J1_15") (pintype "bidirectional"))
    )
    (net (code "137") (name "unconnected-(U$2-GPIO93_L_DD23-PadJ1_61)") (class "Default")
      (node (ref "U$2") (pin "J1_61") (pinfunction "GPIO93_L_DD23_J1_61") (pintype "bidirectional"))
    )
    (net (code "138") (name "unconnected-(U$2-GPIO114_SPI1_NIRQ-PadJ4_41)") (class "Default")
      (node (ref "U$2") (pin "J4_41") (pinfunction "GPIO114_SPI1_NIRQ_J4_41") (pintype "bidirectional"))
    )
    (net (code "139") (name "unconnected-(U$2-GPIO144_GPT9_PWM-PadJ1_18)") (class "Default")
      (node (ref "U$2") (pin "J1_18") (pinfunction "GPIO144_GPT9_PWM_J1_18") (pintype "bidirectional"))
    )
    (net (code "140") (name "unconnected-(U$2-GPIO145_GPT10_PWM-PadJ1_55)") (class "Default")
      (node (ref "U$2") (pin "J1_55") (pinfunction "GPIO145_GPT10_PWM_J1_55") (pintype "bidirectional"))
    )
    (net (code "141") (name "unconnected-(U$2-GPIO146_GPT11_PWM-PadJ1_21)") (class "Default")
      (node (ref "U$2") (pin "J1_21") (pinfunction "GPIO146_GPT11_PWM_J1_21") (pintype "bidirectional"))
    )
    (net (code "142") (name "unconnected-(U$2-GPIO147_GPT8_PWM-PadJ1_16)") (class "Default")
      (node (ref "U$2") (pin "J1_16") (pinfunction "GPIO147_GPT8_PWM_J1_16") (pintype "bidirectional"))
    )
    (net (code "143") (name "unconnected-(U$2-GPIO148_TXD1-PadJ4_24)") (class "Default")
      (node (ref "U$2") (pin "J4_24") (pinfunction "GPIO148_TXD1_J4_24") (pintype "bidirectional"))
    )
    (net (code "144") (name "unconnected-(U$2-GPIO150_MMC3_WP-PadJ4_47)") (class "Default")
      (node (ref "U$2") (pin "J4_47") (pinfunction "GPIO150_MMC3_WP_J4_47") (pintype "bidirectional"))
    )
    (net (code "145") (name "unconnected-(U$2-GPIO151_RXD1-PadJ4_48)") (class "Default")
      (node (ref "U$2") (pin "J4_48") (pinfunction "GPIO151_RXD1_J4_48") (pintype "bidirectional"))
    )
    (net (code "146") (name "unconnected-(U$2-GPIO163_IR_CTS3-PadJ1_22)") (class "Default")
      (node (ref "U$2") (pin "J1_22") (pinfunction "GPIO163_IR_CTS3_J1_22") (pintype "bidirectional"))
    )
    (net (code "147") (name "unconnected-(U$2-GPIO165_IR_RXD3-PadJ1_31)") (class "Default")
      (node (ref "U$2") (pin "J1_31") (pinfunction "GPIO165_IR_RXD3_J1_31") (pintype "bidirectional"))
    )
    (net (code "148") (name "unconnected-(U$2-GPIO166_IR_TXD3-PadJ1_26)") (class "Default")
      (node (ref "U$2") (pin "J1_26") (pinfunction "GPIO166_IR_TXD3_J1_26") (pintype "bidirectional"))
    )
    (net (code "149") (name "unconnected-(U$2-GPIO168_USBH_CPEN-PadJ4_28)") (class "Default")
      (node (ref "U$2") (pin "J4_28") (pinfunction "GPIO168_USBH_CPEN_J4_28") (pintype "bidirectional"))
    )
    (net (code "150") (name "unconnected-(U$2-GPIO170_HDQ_1WIRE-PadJ1_47)") (class "Default")
      (node (ref "U$2") (pin "J1_47") (pinfunction "GPIO170_HDQ_1WIRE_J1_47") (pintype "bidirectional"))
    )
    (net (code "151") (name "unconnected-(U$2-GPIO171_SPI1_CLK-PadJ4_43)") (class "Default")
      (node (ref "U$2") (pin "J4_43") (pinfunction "GPIO171_SPI1_CLK_J4_43") (pintype "bidirectional"))
    )
    (net (code "152") (name "unconnected-(U$2-GPIO172_SPI1_MOSI-PadJ4_44)") (class "Default")
      (node (ref "U$2") (pin "J4_44") (pinfunction "GPIO172_SPI1_MOSI_J4_44") (pintype "bidirectional"))
    )
    (net (code "153") (name "unconnected-(U$2-GPIO173_SPI1_MISO-PadJ4_45)") (class "Default")
      (node (ref "U$2") (pin "J4_45") (pinfunction "GPIO173_SPI1_MISO_J4_45") (pintype "bidirectional"))
    )
    (net (code "154") (name "unconnected-(U$2-GPIO174_SPI1_CS0-PadJ4_27)") (class "Default")
      (node (ref "U$2") (pin "J4_27") (pinfunction "GPIO174_SPI1_CS0_J4_27") (pintype "bidirectional"))
    )
    (net (code "155") (name "unconnected-(U$2-GPIO175_SPI1_CS1-PadJ4_42)") (class "Default")
      (node (ref "U$2") (pin "J4_42") (pinfunction "GPIO175_SPI1_CS1_J4_42") (pintype "bidirectional"))
    )
    (net (code "156") (name "unconnected-(U$2-GPIO176_ETH0_IRQ-PadJ4_25)") (class "Default")
      (node (ref "U$2") (pin "J4_25") (pinfunction "GPIO176_ETH0_IRQ_J4_25") (pintype "bidirectional"))
    )
    (net (code "157") (name "unconnected-(U$2-GPIO184_I2C3_SCL-PadJ1_13)") (class "Default")
      (node (ref "U$2") (pin "J1_13") (pinfunction "GPIO184_I2C3_SCL_J1_13") (pintype "bidirectional"))
    )
    (net (code "158") (name "unconnected-(U$2-GPIO185_I2C3_SDA-PadJ1_10)") (class "Default")
      (node (ref "U$2") (pin "J1_10") (pinfunction "GPIO185_I2C3_SDA_J1_10") (pintype "bidirectional"))
    )
    (net (code "159") (name "unconnected-(U$2-GPIO186_GPS_PPS-PadJ1_14)") (class "Default")
      (node (ref "U$2") (pin "J1_14") (pinfunction "GPIO186_GPS_PPS_J1_14") (pintype "bidirectional"))
    )
    (net (code "160") (name "unconnected-(U$2-HSOLF-PadJ1_68)") (class "Default")
      (node (ref "U$2") (pin "J1_68") (pinfunction "HSOLF_J1_68") (pintype "bidirectional"))
    )
    (net (code "161") (name "unconnected-(U$2-HSORF-PadJ1_69)") (class "Default")
      (node (ref "U$2") (pin "J1_69") (pinfunction "HSORF_J1_69") (pintype "bidirectional"))
    )
    (net (code "162") (name "unconnected-(U$2-MIC_MAIN_MF-PadJ1_57)") (class "Default")
      (node (ref "U$2") (pin "J1_57") (pinfunction "MIC_MAIN_MF_J1_57") (pintype "bidirectional"))
    )
    (net (code "163") (name "unconnected-(U$2-MIC_SUB_MF-PadJ1_39)") (class "Default")
      (node (ref "U$2") (pin "J1_39") (pinfunction "MIC_SUB_MF_J1_39") (pintype "bidirectional"))
    )
    (net (code "164") (name "unconnected-(U$2-N_MANUAL_RESET-PadJ1_1)") (class "Default")
      (node (ref "U$2") (pin "J1_1") (pinfunction "N_MANUAL_RESET_J1_1") (pintype "bidirectional"))
    )
    (net (code "165") (name "unconnected-(U$2-POWERON-PadJ1_65)") (class "Default")
      (node (ref "U$2") (pin "J1_65") (pinfunction "POWERON_J1_65") (pintype "bidirectional"))
    )
    (net (code "166") (name "unconnected-(U$2-PWM0-PadJ1_42)") (class "Default")
      (node (ref "U$2") (pin "J1_42") (pinfunction "PWM0_J1_42") (pintype "bidirectional"))
    )
    (net (code "167") (name "unconnected-(U$2-PWM1-PadJ1_49)") (class "Default")
      (node (ref "U$2") (pin "J1_49") (pinfunction "PWM1_J1_49") (pintype "bidirectional"))
    )
    (net (code "168") (name "unconnected-(U$2-SYSEN-PadJ1_59)") (class "Default")
      (node (ref "U$2") (pin "J1_59") (pinfunction "SYSEN_J1_59") (pintype "bidirectional"))
    )
    (net (code "169") (name "unconnected-(U$2-TV_OUT1-PadJ1_63)") (class "Default")
      (node (ref "U$2") (pin "J1_63") (pinfunction "TV_OUT1_J1_63") (pintype "bidirectional"))
    )
    (net (code "170") (name "unconnected-(U$2-TV_OUT2-PadJ1_62)") (class "Default")
      (node (ref "U$2") (pin "J1_62") (pinfunction "TV_OUT2_J1_62") (pintype "bidirectional"))
    )
    (net (code "171") (name "unconnected-(U$2-USBH_DM-PadJ4_35)") (class "Default")
      (node (ref "U$2") (pin "J4_35") (pinfunction "USBH_DM_J4_35") (pintype "bidirectional"))
    )
    (net (code "172") (name "unconnected-(U$2-USBH_DP-PadJ4_34)") (class "Default")
      (node (ref "U$2") (pin "J4_34") (pinfunction "USBH_DP_J4_34") (pintype "bidirectional"))
    )
    (net (code "173") (name "unconnected-(U$2-USBH_VBUS-PadJ4_32)") (class "Default")
      (node (ref "U$2") (pin "J4_32") (pinfunction "USBH_VBUS_J4_32") (pintype "bidirectional"))
    )
    (net (code "174") (name "unconnected-(U$2-USBOTG_DM-PadJ1_37)") (class "Default")
      (node (ref "U$2") (pin "J1_37") (pinfunction "USBOTG_DM_J1_37") (pintype "bidirectional"))
    )
    (net (code "175") (name "unconnected-(U$2-USBOTG_DP-PadJ1_36)") (class "Default")
      (node (ref "U$2") (pin "J1_36") (pinfunction "USBOTG_DP_J1_36") (pintype "bidirectional"))
    )
    (net (code "176") (name "unconnected-(U$2-USBOTG_ID-PadJ1_46)") (class "Default")
      (node (ref "U$2") (pin "J1_46") (pinfunction "USBOTG_ID_J1_46") (pintype "bidirectional"))
    )
    (net (code "177") (name "unconnected-(U$2-USBOTG_VBUS-PadJ1_54)") (class "Default")
      (node (ref "U$2") (pin "J1_54") (pinfunction "USBOTG_VBUS_J1_54") (pintype "bidirectional"))
    )
    (net (code "178") (name "unconnected-(U$2-VBACKUP-PadJ1_52)") (class "Default")
      (node (ref "U$2") (pin "J1_52") (pinfunction "VBACKUP_J1_52") (pintype "bidirectional"))
    )
    (net (code "179") (name "unconnected-(U$2-VSYSTEM-PadJ1_66)") (class "Default")
      (node (ref "U$2") (pin "J1_66") (pinfunction "VSYSTEM_J1_66") (pintype "bidirectional"))
    )
    (net (code "180") (name "unconnected-(U$2-VSYSTEM-PadJ1_67)") (class "Default")
      (node (ref "U$2") (pin "J1_67") (pinfunction "VSYSTEM_J1_67") (pintype "bidirectional"))
    )
    (net (code "181") (name "unconnected-(U$2-VSYSTEM-PadJ4_1)") (class "Default")
      (node (ref "U$2") (pin "J4_1") (pinfunction "VSYSTEM_J4_1") (pintype "bidirectional"))
    )
    (net (code "182") (name "unconnected-(U$2-VSYSTEM-PadJ4_2)") (class "Default")
      (node (ref "U$2") (pin "J4_2") (pinfunction "VSYSTEM_J4_2") (pintype "bidirectional"))
    )
  )
)
